# Power.net
KiCad netlist of a schematic drawn in Altium Designer
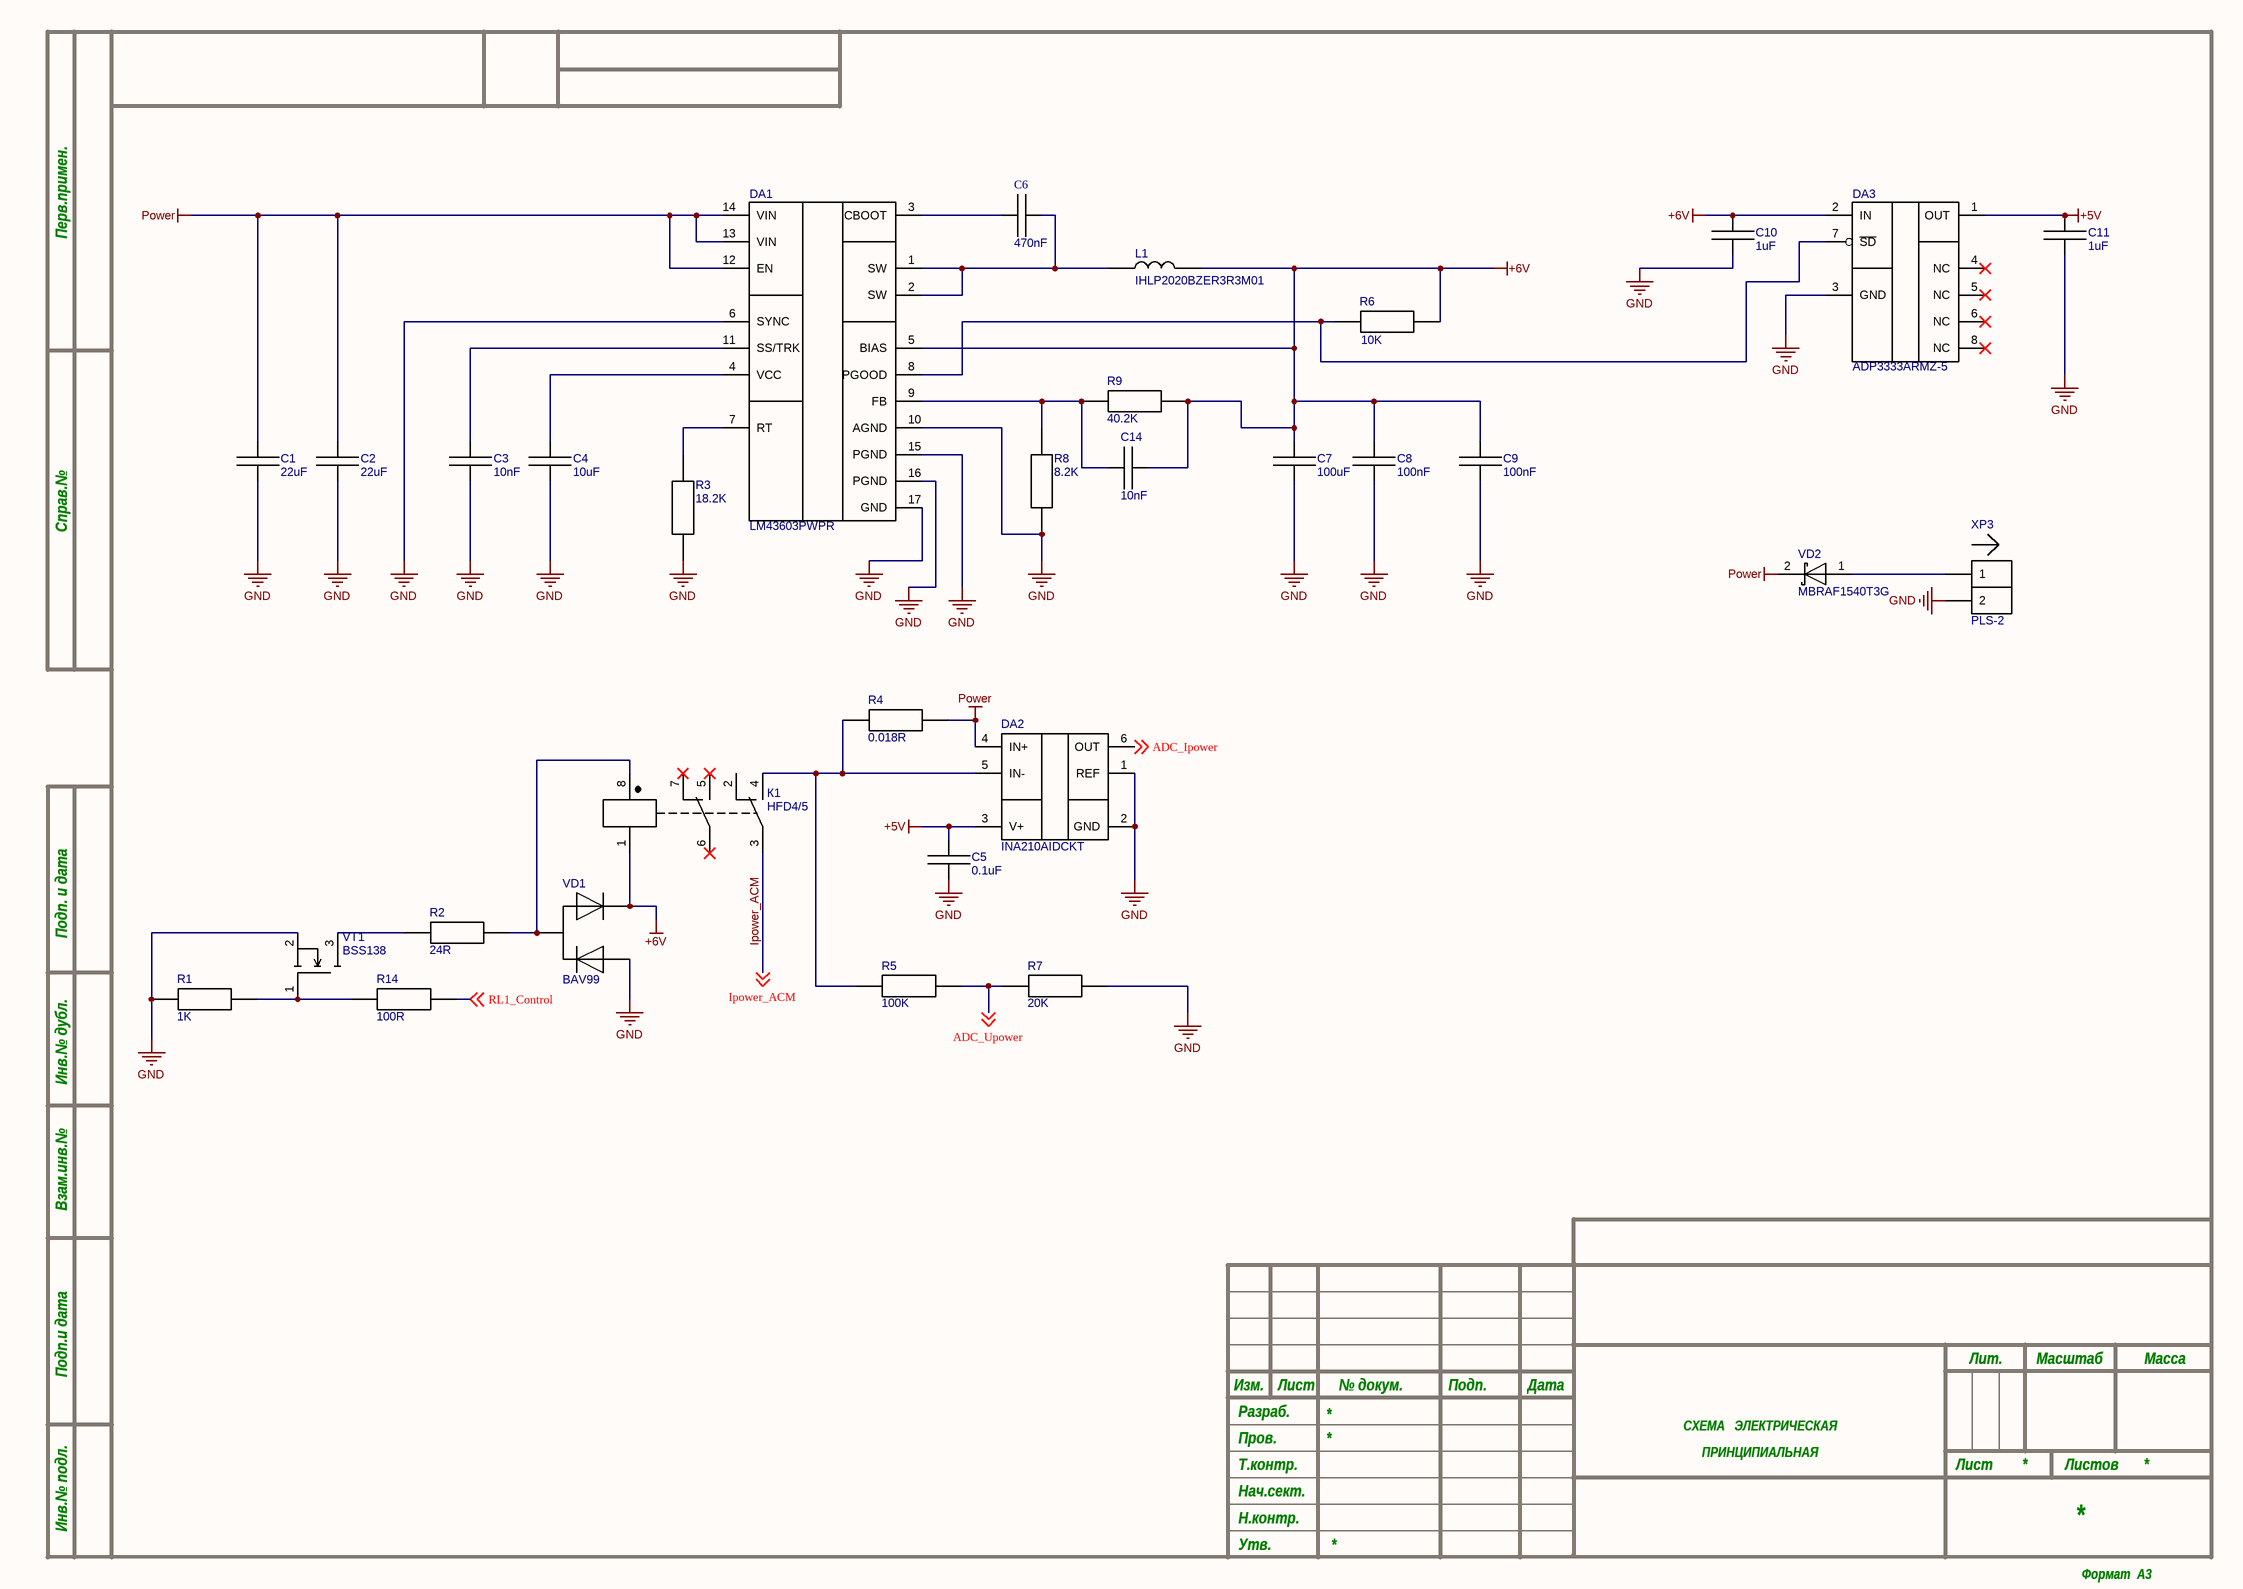
[diagram p0: Power.SchDoc]

(export (version "E")
  (design (tool "Eeschema 10.0.6"))
  (components
    (comp (ref "C1")
      (value "22uF")
      (footprint "1210C")
      (description "C1210-22uF 10% 50V")
      (fields (field (name "PART NUMBER") "SMD CAP CER 22uF ±10% 50V X7R 1210"))
      (libsource (lib "Test_Stand_Pergam") (part "C1210-22uF 10% 50V"))
    )
    (comp (ref "C2")
      (value "22uF")
      (footprint "1210C")
      (description "C1210-22uF 10% 50V")
      (fields (field (name "PART NUMBER") "SMD CAP CER 22uF ±10% 50V X7R 1210"))
      (libsource (lib "Test_Stand_Pergam") (part "C1210-22uF 10% 50V"))
    )
    (comp (ref "C3")
      (value "10nF")
      (footprint "0402C")
      (description "C0402-10nF 10% 50V")
      (fields
        (field (name "PART NUMBER") "SMD CAP CER 10nF ±10% 50V X5R 0402")
        (field (name "ADDED_BY") "Rutel@Mail.ru")
      )
      (libsource (lib "Test_Stand_Pergam") (part "C0402-10nF 10% 50V"))
    )
    (comp (ref "C4")
      (value "10uF")
      (footprint "0402C")
      (description "C0402-10UF 10% 10V")
      (fields
        (field (name "PART NUMBER") "SMD CAP CER 10UF ±10% 10V X5R 0402")
        (field (name "ADDED_BY") "Rutel@Mail.ru")
      )
      (libsource (lib "Test_Stand_Pergam") (part "C0402-10UF 10% 10V"))
    )
    (comp (ref "C5")
      (value "0.1uF")
      (footprint "0603C")
      (description "C0603 0.1UF 10% 50V")
      (fields
        (field (name "PART NUMBER") "SMD CAP CER 0.1UF ±10% 50V X7R 0603")
        (field (name "ADDED_BY") "anton@teslatec.ru")
      )
      (libsource (lib "Test_Stand_Pergam") (part "C0603-0.1UF 10% 50V"))
    )
    (comp (ref "C6")
      (value "470nF")
      (footprint "0402C")
      (description "C0402-470nF 10% 50V")
      (fields (field (name "PART NUMBER") "SMD CAP CER 470nF ±10% 50V X5R 0402"))
      (libsource (lib "Test_Stand_Pergam") (part "C0402-470nF 10% 50V"))
    )
    (comp (ref "C7")
      (value "100uF")
      (footprint "1210C")
      (description "C1210-100UF 10% 16V")
      (fields (field (name "PART NUMBER") "SMD CAP CER 100UF ±10% 16V X7R 1210"))
      (libsource (lib "Test_Stand_Pergam") (part "C1210-100UF 10% 16V"))
    )
    (comp (ref "C8")
      (value "100nF")
      (footprint "0402C")
      (description "C0402-100nF 10% 50V")
      (fields
        (field (name "PART NUMBER") "SMD CAP CER 100nF ±10% 50V X5R 0402")
        (field (name "ADDED_BY") "Rutel@Mail.ru")
      )
      (libsource (lib "Test_Stand_Pergam") (part "C0402-100nF 10% 50V"))
    )
    (comp (ref "C9")
      (value "100nF")
      (footprint "0402C")
      (description "C0402-100nF 10% 50V")
      (fields
        (field (name "PART NUMBER") "SMD CAP CER 100nF ±10% 50V X5R 0402")
        (field (name "ADDED_BY") "Rutel@Mail.ru")
      )
      (libsource (lib "Test_Stand_Pergam") (part "C0402-100nF 10% 50V"))
    )
    (comp (ref "C10")
      (value "1uF")
      (footprint "0603C")
      (description "C0603-1uF 10% 50V")
      (fields
        (field (name "PART NUMBER") "SMD CAP CER 1uF ±10% 50V X7R 0603")
        (field (name "ADDED_BY") "grebelny_av@teslatec.ru")
      )
      (libsource (lib "Test_Stand_Pergam") (part "C0603-1uF 10% 50V"))
    )
    (comp (ref "C11")
      (value "1uF")
      (footprint "0603C")
      (description "C0603-1uF 10% 50V")
      (fields
        (field (name "PART NUMBER") "SMD CAP CER 1uF ±10% 50V X7R 0603")
        (field (name "ADDED_BY") "grebelny_av@teslatec.ru")
      )
      (libsource (lib "Test_Stand_Pergam") (part "C0603-1uF 10% 50V"))
    )
    (comp (ref "C14")
      (value "10nF")
      (footprint "0402C")
      (description "C0402-10nF 10% 50V")
      (fields
        (field (name "PART NUMBER") "SMD CAP CER 10nF ±10% 50V X5R 0402")
        (field (name "ADDED_BY") "Rutel@Mail.ru")
      )
      (libsource (lib "Test_Stand_Pergam") (part "C0402-10nF 10% 50V"))
    )
    (comp (ref "DA1")
      (value "LM43603PWPR")
      (footprint "TSSOP-17")
      (description "LM43603PWPR 3.5-V to 36-V, 3-A Synchronous Step-Down Voltage Converter")
      (fields (field (name "ADDED_BY") "irdolgopolowa@yandex.ru"))
      (libsource (lib "Test_Stand_Pergam") (part "LM43603PWPR"))
    )
    (comp (ref "DA2")
      (value "INA210AIDCKT")
      (footprint "SC-70-6")
      (description "26V, 14kHz, bi-directional, package SC70-6, -40 to 125")
      (fields (field (name "ADDED_BY") "ridel_av@teslatec.ru"))
      (libsource (lib "Test_Stand_Pergam") (part "INA210AIDCKT"))
    )
    (comp (ref "DA3")
      (value "ADP3333ARMZ-5")
      (footprint "MSOP-8")
      (description "5V 300 mA, Low Dropout,\r\nCMOS Linear Regulator")
      (fields (field (name "ADDED_BY") "irdolgopolowa@yandex.ru"))
      (libsource (lib "Test_Stand_Pergam") (part "ADP3333ARMZ-5"))
    )
    (comp (ref "L1")
      (value "IHLP2020BZER3R3M01")
      (footprint "IHLP2020CZ-01")
      (description "FIXED IND 3.3UH 3.3A 79 MOHM SMD")
      (fields (field (name "ADDED_BY") "Rutel@teslatec.ru"))
      (libsource (lib "Test_Stand_Pergam") (part "IHLP2020BZER3R3M01"))
    )
    (comp (ref "R1")
      (value "1K")
      (footprint "R0402")
      (description "Resistor SMD 1K 1% 0402")
      (fields
        (field (name "PART NUMBER") "SMD RES 1 KOHM 1% ±100ppm/°C 0402")
        (field (name "ADDED_BY") "irdolgopolowa@yandex.ru")
      )
      (libsource (lib "Test_Stand_Pergam") (part "R0402-1K"))
    )
    (comp (ref "R2")
      (value "24R")
      (footprint "R0402")
      (description "Resistor SMD 24R 1% 0402")
      (fields
        (field (name "PART NUMBER") "SMD RES 24R OHM 1% ±100ppm/°C 0402")
        (field (name "ADDED_BY") "Rutel@teslatec.ru")
      )
      (libsource (lib "Test_Stand_Pergam") (part "R0402-24R"))
    )
    (comp (ref "R3")
      (value "18.2K")
      (footprint "R0402")
      (description "Resistor SMD 18.2K 1% 0402")
      (fields
        (field (name "PART NUMBER") "SMD RES 18.2 KOHM 1% ±100ppm/°C 0402")
        (field (name "ADDED_BY") "Rutel@teslatec.ru")
      )
      (libsource (lib "Test_Stand_Pergam") (part "R0402-18.2K"))
    )
    (comp (ref "R4")
      (value "0.018R")
      (footprint "R1206")
      (description "Resistor SMD 0.018R 1% 1206")
      (fields
        (field (name "PART NUMBER") "TL2BR018F SMD RES 0.018 OHM 1% ±75ppm/°C 1206")
        (field (name "ADDED_BY") "irdolgopolowa@yandex.ru")
      )
      (libsource (lib "Test_Stand_Pergam") (part "R1206-0.018R"))
    )
    (comp (ref "R5")
      (value "100K")
      (footprint "R0402")
      (description "Resistor SMD 100K 1% 0402")
      (fields
        (field (name "PART NUMBER") "SMD RES 100 KOHM 1% ±100ppm/°C 0402")
        (field (name "ADDED_BY") "Rutel@teslatec.ru")
      )
      (libsource (lib "Test_Stand_Pergam") (part "R0402-100K"))
    )
    (comp (ref "R6")
      (value "10K")
      (footprint "R0402")
      (description "Resistor SMD 10K 1% 0402")
      (fields
        (field (name "PART NUMBER") "SMD RES 10 KOHM 1% ±100ppm/°C 0402")
        (field (name "ADDED_BY") "Rutel@teslatec.ru")
      )
      (libsource (lib "Test_Stand_Pergam") (part "R0402-10K"))
    )
    (comp (ref "R7")
      (value "20K")
      (footprint "R0402")
      (description "Resistor SMD 20K 1% 0402")
      (fields
        (field (name "PART NUMBER") "SMD RES 20 KOHM 1% ±100ppm/°C 0402")
        (field (name "ADDED_BY") "Rutel@teslatec.ru")
      )
      (libsource (lib "Test_Stand_Pergam") (part "R0402-20K"))
    )
    (comp (ref "R8")
      (value "8.2K")
      (footprint "R0402")
      (description "Resistor SMD 8.2K 1% 0402")
      (fields
        (field (name "PART NUMBER") "SMD RES 8.2 KOHM 1% ±100ppm/°C 0402")
        (field (name "ADDED_BY") "Rutel@teslatec.ru")
      )
      (libsource (lib "Test_Stand_Pergam") (part "R0402-8.2K"))
    )
    (comp (ref "R9")
      (value "40.2K")
      (footprint "R0402")
      (description "Resistor SMD 40.2K 1% 0402")
      (fields
        (field (name "PART NUMBER") "SMD RES 40.2K KOHM 1% ±100ppm/°C 0402")
        (field (name "ADDED_BY") "ridel_av@teslatec.ru")
      )
      (libsource (lib "Test_Stand_Pergam") (part "R0402-40.2K"))
    )
    (comp (ref "R14")
      (value "100R")
      (footprint "R0402")
      (description "Resistor SMD 100R 1% 0402")
      (fields
        (field (name "PART NUMBER") "SMD RES 100 OHM 1% ±100ppm/°C 0402")
        (field (name "ADDED_BY") "irdolgopolowa@yandex.ru")
      )
      (libsource (lib "Test_Stand_Pergam") (part "R0402-100R"))
    )
    (comp (ref "VD1")
      (value "BAV99")
      (footprint "SOT-23-3")
      (description "BAV99, UMW, 70В, 200мА")
      (fields (field (name "ADDED_BY") "andrew@teslatec.ru"))
      (libsource (lib "Test_Stand_Pergam") (part "BAV99"))
    )
    (comp (ref "VD2")
      (value "MBRAF1540T3G")
      (footprint "SMA-FL")
      (description "1.5 A, 40 V Schottky Rectifier")
      (fields (field (name "ADDED_BY") "irdolgopolowa@yandex.ru"))
      (libsource (lib "Test_Stand_Pergam") (part "MBRAF1540T3G"))
    )
    (comp (ref "VT1")
      (value "BSS138")
      (footprint "SOT-23-3")
      (description "N-Channel Logic Level Enhancement Mode Field Effect Transistor")
      (fields (field (name "ADDED_BY") "ma_lubushkin@teslatec.ru"))
      (libsource (lib "Test_Stand_Pergam") (part "BSS138"))
    )
    (comp (ref "XP3")
      (value "PLS-2")
      (footprint "PLS-2")
      (description "HEADER 2.54mm")
      (fields (field (name "ADDED_BY") "irdolgopolowa@yandex.ru"))
      (libsource (lib "Test_Stand_Pergam") (part "PLS-2"))
    )
    (comp (ref "К1")
      (value "HFD4/5")
      (footprint "DIP-8")
      (description "HFD4/5 (IM03TS) (1-1462037-8), 5VDC, 2A/250VAC DPDT")
      (fields (field (name "PART NUMBER") "HFD4/5SR") (field (name "ADDED_BY") "irdolgopolowa@yandex.ru"))
      (libsource (lib "Test_Stand_Pergam") (part "HFD4/5"))
    )
  )
  (nets
    (net (code "1") (name "+5V") (class "Default")
      (node (ref "C11") (pin "2") (pinfunction "2_2") (pintype "passive"))
      (node (ref "C5") (pin "2") (pinfunction "2_2") (pintype "passive"))
      (node (ref "DA2") (pin "3") (pinfunction "V+_3") (pintype "passive"))
      (node (ref "DA3") (pin "1") (pinfunction "OUT_1") (pintype "passive"))
    )
    (net (code "2") (name "+6V") (class "Default")
      (node (ref "C10") (pin "2") (pinfunction "2_2") (pintype "passive"))
      (node (ref "C14") (pin "2") (pinfunction "2_2") (pintype "passive"))
      (node (ref "C7") (pin "2") (pinfunction "2_2") (pintype "passive"))
      (node (ref "C8") (pin "2") (pinfunction "2_2") (pintype "passive"))
      (node (ref "C9") (pin "2") (pinfunction "2_2") (pintype "passive"))
      (node (ref "DA1") (pin "5") (pinfunction "BIAS_5") (pintype "passive"))
      (node (ref "DA3") (pin "2") (pinfunction "IN_2") (pintype "passive"))
      (node (ref "L1") (pin "2") (pinfunction "2_2") (pintype "passive"))
      (node (ref "R6") (pin "2") (pinfunction "2_2") (pintype "passive"))
      (node (ref "R9") (pin "2") (pinfunction "2_2") (pintype "passive"))
      (node (ref "VD1") (pin "2") (pinfunction "2_2") (pintype "passive"))
      (node (ref "К1") (pin "1") (pinfunction "1_1") (pintype "passive"))
    )
    (net (code "3") (name "ADC_Ipower") (class "Default")
      (node (ref "DA2") (pin "6") (pinfunction "OUT_6") (pintype "passive"))
    )
    (net (code "4") (name "ADC_Upower") (class "Default")
      (node (ref "R5") (pin "2") (pinfunction "2_2") (pintype "passive"))
      (node (ref "R7") (pin "1") (pinfunction "1_1") (pintype "passive"))
    )
    (net (code "5") (name "GND") (class "Default")
      (node (ref "C1") (pin "1") (pinfunction "1_1") (pintype "passive"))
      (node (ref "C10") (pin "1") (pinfunction "1_1") (pintype "passive"))
      (node (ref "C11") (pin "1") (pinfunction "1_1") (pintype "passive"))
      (node (ref "C2") (pin "1") (pinfunction "1_1") (pintype "passive"))
      (node (ref "C3") (pin "1") (pinfunction "1_1") (pintype "passive"))
      (node (ref "C4") (pin "1") (pinfunction "1_1") (pintype "passive"))
      (node (ref "C5") (pin "1") (pinfunction "1_1") (pintype "passive"))
      (node (ref "C7") (pin "1") (pinfunction "1_1") (pintype "passive"))
      (node (ref "C8") (pin "1") (pinfunction "1_1") (pintype "passive"))
      (node (ref "C9") (pin "1") (pinfunction "1_1") (pintype "passive"))
      (node (ref "DA1") (pin "10") (pinfunction "AGND_10") (pintype "passive"))
      (node (ref "DA1") (pin "15") (pinfunction "PGND_15") (pintype "passive"))
      (node (ref "DA1") (pin "16") (pinfunction "PGND_16") (pintype "passive"))
      (node (ref "DA1") (pin "17") (pinfunction "GND_17") (pintype "passive"))
      (node (ref "DA1") (pin "6") (pinfunction "SYNC_6") (pintype "passive"))
      (node (ref "DA2") (pin "1") (pinfunction "REF_1") (pintype "passive"))
      (node (ref "DA2") (pin "2") (pinfunction "GND_2") (pintype "passive"))
      (node (ref "DA3") (pin "3") (pinfunction "GND_3") (pintype "passive"))
      (node (ref "R1") (pin "1") (pinfunction "1_1") (pintype "passive"))
      (node (ref "R3") (pin "1") (pinfunction "1_1") (pintype "passive"))
      (node (ref "R7") (pin "2") (pinfunction "2_2") (pintype "passive"))
      (node (ref "R8") (pin "1") (pinfunction "1_1") (pintype "passive"))
      (node (ref "VD1") (pin "1") (pinfunction "1_1") (pintype "passive"))
      (node (ref "VT1") (pin "2") (pinfunction "2_2") (pintype "passive"))
      (node (ref "XP3") (pin "2") (pinfunction "2_2") (pintype "passive"))
    )
    (net (code "6") (name "Ipower_ACM") (class "Default")
      (node (ref "К1") (pin "3") (pinfunction "3_3") (pintype "passive"))
    )
    (net (code "7") (name "Net-(C6-Pad2)") (class "Default")
      (node (ref "C6") (pin "2") (pinfunction "2_2") (pintype "passive"))
      (node (ref "DA1") (pin "1") (pinfunction "SW_1") (pintype "passive"))
      (node (ref "DA1") (pin "2") (pinfunction "SW_2") (pintype "passive"))
      (node (ref "L1") (pin "1") (pinfunction "1_1") (pintype "passive"))
    )
    (net (code "8") (name "Net-(DA1-CBOOT)") (class "Default")
      (node (ref "C6") (pin "1") (pinfunction "1_1") (pintype "passive"))
      (node (ref "DA1") (pin "3") (pinfunction "CBOOT_3") (pintype "passive"))
    )
    (net (code "9") (name "Net-(DA1-FB)") (class "Default")
      (node (ref "C14") (pin "1") (pinfunction "1_1") (pintype "passive"))
      (node (ref "DA1") (pin "9") (pinfunction "FB_9") (pintype "passive"))
      (node (ref "R8") (pin "2") (pinfunction "2_2") (pintype "passive"))
      (node (ref "R9") (pin "1") (pinfunction "1_1") (pintype "passive"))
    )
    (net (code "10") (name "Net-(DA1-PGOOD)") (class "Default")
      (node (ref "DA1") (pin "8") (pinfunction "PGOOD_8") (pintype "passive"))
      (node (ref "DA3") (pin "7") (pinfunction "~{SD}_7") (pintype "passive"))
      (node (ref "R6") (pin "1") (pinfunction "1_1") (pintype "passive"))
    )
    (net (code "11") (name "Net-(DA1-RT)") (class "Default")
      (node (ref "DA1") (pin "7") (pinfunction "RT_7") (pintype "passive"))
      (node (ref "R3") (pin "2") (pinfunction "2_2") (pintype "passive"))
    )
    (net (code "12") (name "Net-(DA1-SS{slash}TRK)") (class "Default")
      (node (ref "C3") (pin "2") (pinfunction "2_2") (pintype "passive"))
      (node (ref "DA1") (pin "11") (pinfunction "SS/TRK_11") (pintype "passive"))
    )
    (net (code "13") (name "Net-(DA1-VCC)") (class "Default")
      (node (ref "C4") (pin "2") (pinfunction "2_2") (pintype "passive"))
      (node (ref "DA1") (pin "4") (pinfunction "VCC_4") (pintype "passive"))
    )
    (net (code "14") (name "Net-(DA2-IN-)") (class "Default")
      (node (ref "DA2") (pin "5") (pinfunction "IN-_5") (pintype "passive"))
      (node (ref "R4") (pin "2") (pinfunction "2_2") (pintype "passive"))
      (node (ref "R5") (pin "1") (pinfunction "1_1") (pintype "passive"))
      (node (ref "К1") (pin "4") (pinfunction "4_4") (pintype "passive"))
    )
    (net (code "15") (name "Net-(R1-Pad2)") (class "Default")
      (node (ref "R1") (pin "2") (pinfunction "2_2") (pintype "passive"))
      (node (ref "R14") (pin "1") (pinfunction "1_1") (pintype "passive"))
      (node (ref "VT1") (pin "1") (pinfunction "1_1") (pintype "passive"))
    )
    (net (code "16") (name "Net-(R2-Pad1)") (class "Default")
      (node (ref "R2") (pin "1") (pinfunction "1_1") (pintype "passive"))
      (node (ref "VT1") (pin "3") (pinfunction "3_3") (pintype "passive"))
    )
    (net (code "17") (name "Net-(R2-Pad2)") (class "Default")
      (node (ref "R2") (pin "2") (pinfunction "2_2") (pintype "passive"))
      (node (ref "VD1") (pin "3") (pinfunction "3_3") (pintype "passive"))
      (node (ref "К1") (pin "8") (pinfunction "8_8") (pintype "passive"))
    )
    (net (code "18") (name "Net-(VD2-Pad1)") (class "Default")
      (node (ref "VD2") (pin "1") (pinfunction "1_1") (pintype "passive"))
      (node (ref "XP3") (pin "1") (pinfunction "1_1") (pintype "passive"))
    )
    (net (code "19") (name "Power") (class "Default")
      (node (ref "C1") (pin "2") (pinfunction "2_2") (pintype "passive"))
      (node (ref "C2") (pin "2") (pinfunction "2_2") (pintype "passive"))
      (node (ref "DA1") (pin "12") (pinfunction "EN_12") (pintype "passive"))
      (node (ref "DA1") (pin "13") (pinfunction "VIN_13") (pintype "passive"))
      (node (ref "DA1") (pin "14") (pinfunction "VIN_14") (pintype "passive"))
      (node (ref "DA2") (pin "4") (pinfunction "IN+_4") (pintype "passive"))
      (node (ref "R4") (pin "1") (pinfunction "1_1") (pintype "passive"))
      (node (ref "VD2") (pin "2") (pinfunction "2_2") (pintype "passive"))
    )
    (net (code "20") (name "RL1_Control") (class "Default")
      (node (ref "R14") (pin "2") (pinfunction "2_2") (pintype "passive"))
    )
    (net (code "21") (name "unconnected-(DA3-NC-Pad4)") (class "Default")
      (node (ref "DA3") (pin "4") (pinfunction "NC_4") (pintype "passive+no_connect"))
    )
    (net (code "22") (name "unconnected-(DA3-NC-Pad5)") (class "Default")
      (node (ref "DA3") (pin "5") (pinfunction "NC_5") (pintype "passive+no_connect"))
    )
    (net (code "23") (name "unconnected-(DA3-NC-Pad6)") (class "Default")
      (node (ref "DA3") (pin "6") (pinfunction "NC_6") (pintype "passive+no_connect"))
    )
    (net (code "24") (name "unconnected-(DA3-NC-Pad8)") (class "Default")
      (node (ref "DA3") (pin "8") (pinfunction "NC_8") (pintype "passive+no_connect"))
    )
    (net (code "25") (name "unconnected-(К1-Pad2)") (class "Default")
      (node (ref "К1") (pin "2") (pinfunction "2_2") (pintype "passive"))
    )
    (net (code "26") (name "unconnected-(К1-Pad5)") (class "Default")
      (node (ref "К1") (pin "5") (pinfunction "5_5") (pintype "passive+no_connect"))
    )
    (net (code "27") (name "unconnected-(К1-Pad6)") (class "Default")
      (node (ref "К1") (pin "6") (pinfunction "6_6") (pintype "passive+no_connect"))
    )
    (net (code "28") (name "unconnected-(К1-Pad7)") (class "Default")
      (node (ref "К1") (pin "7") (pinfunction "7_7") (pintype "passive+no_connect"))
    )
  )
)
